# 00_Overview.net
KiCad netlist of a schematic drawn in Altium Designer
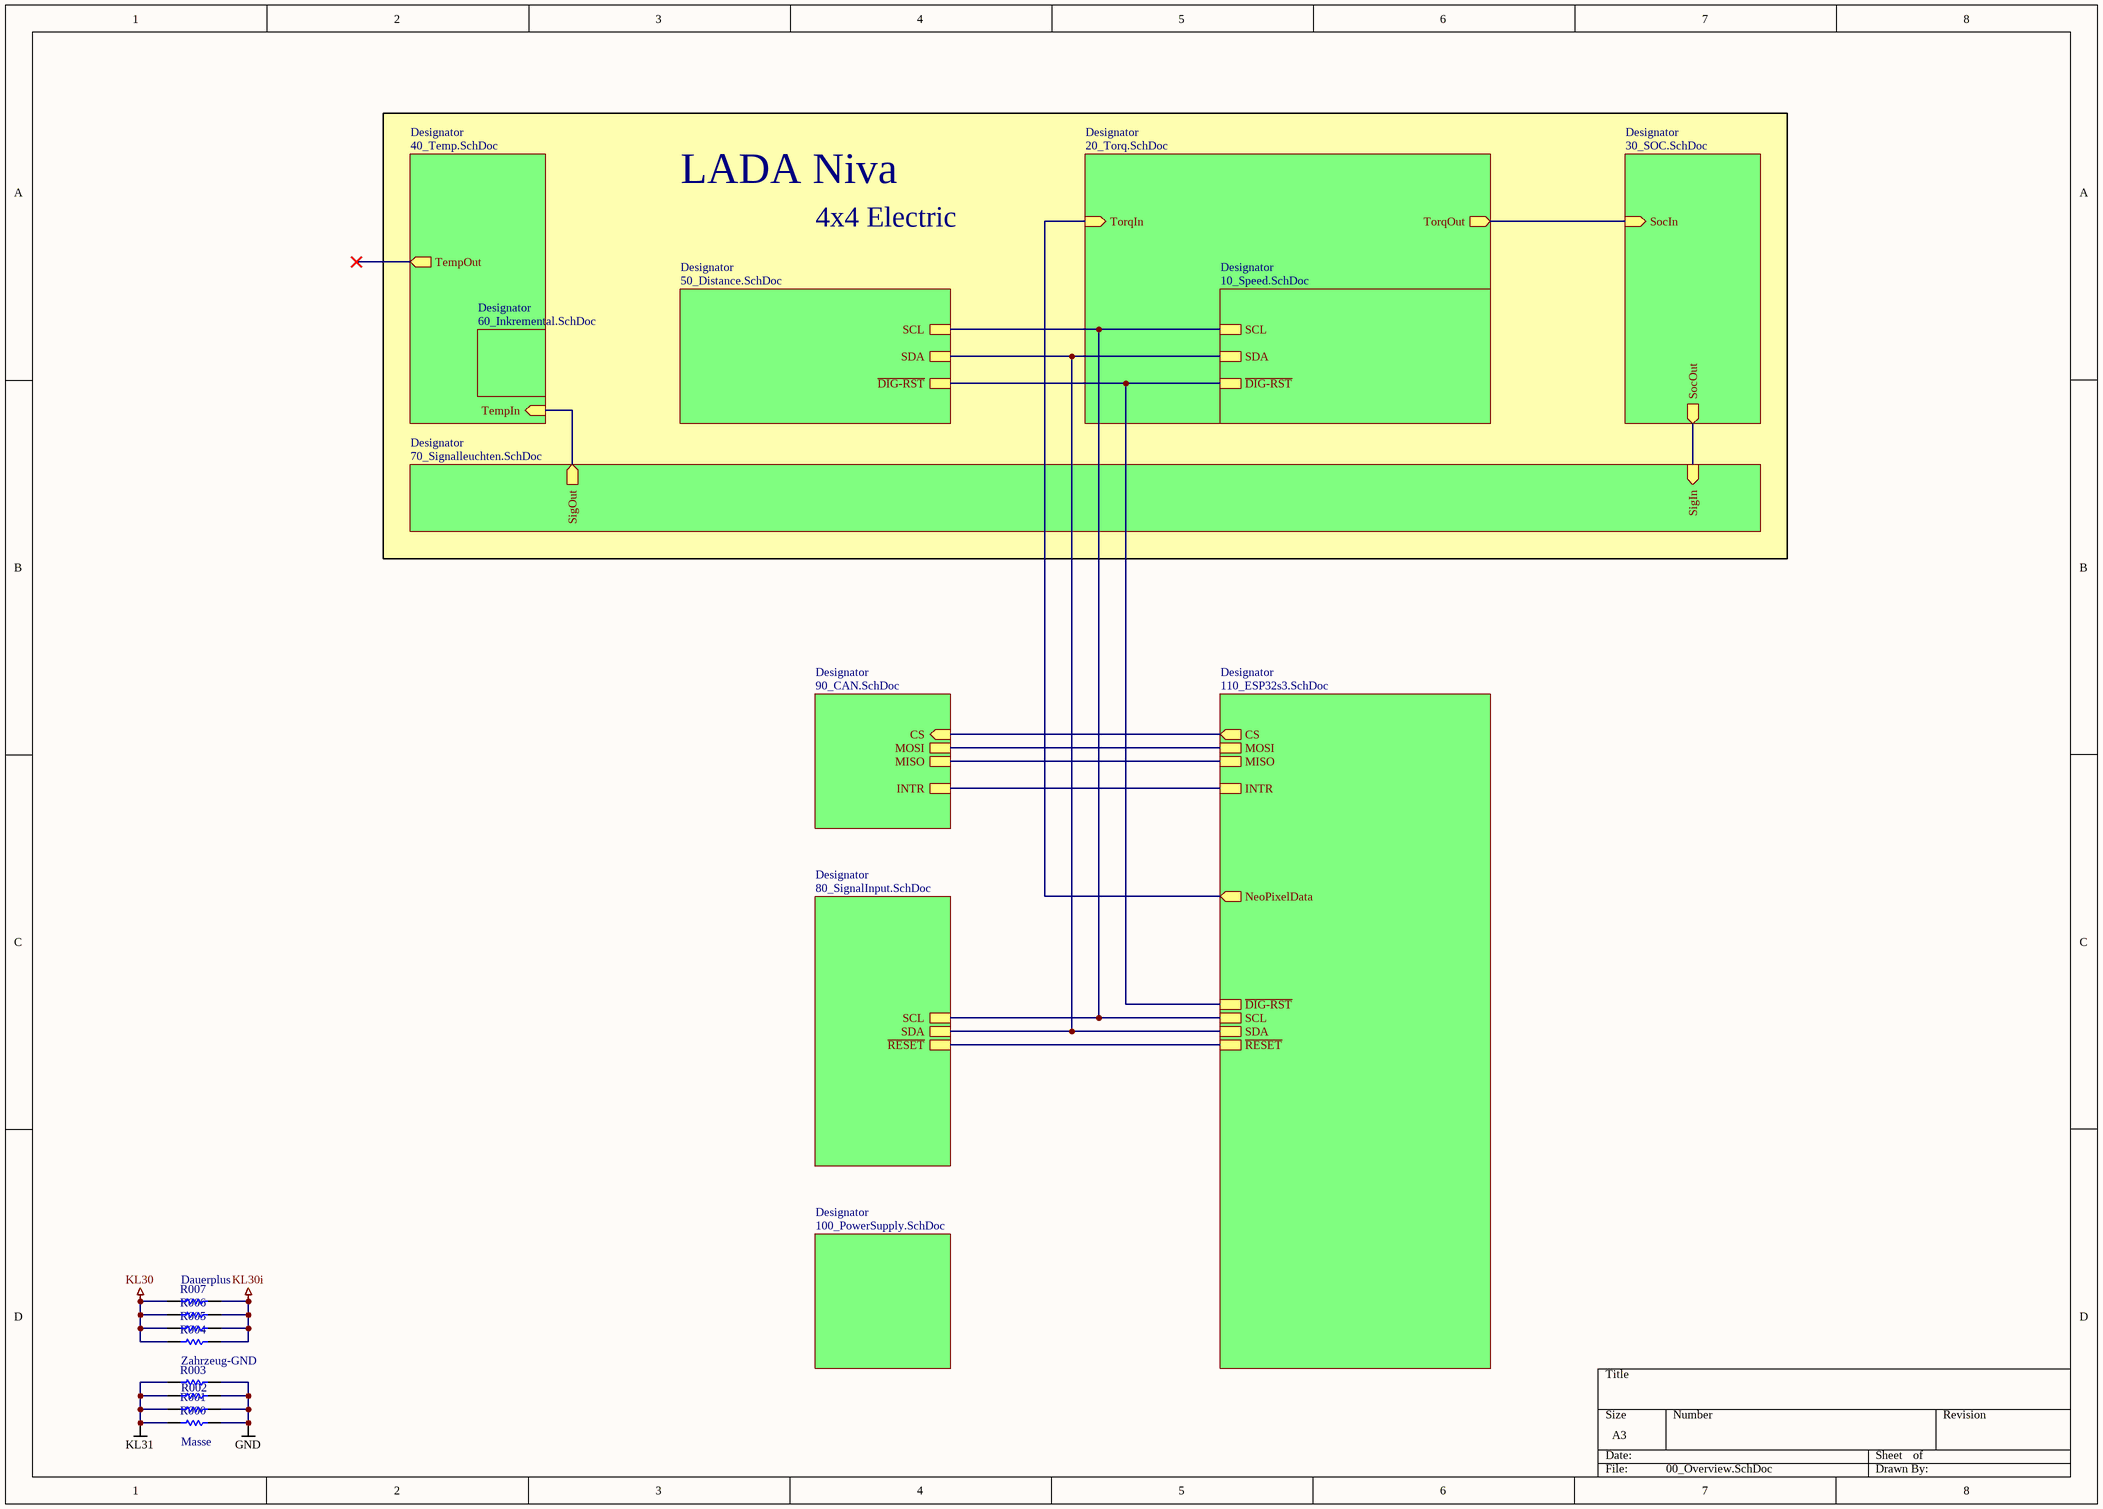
[diagram p0: 00_Overview.SchDoc]

(export (version "E")
  (design (tool "Eeschema 10.0.6"))
  (components
    (comp (ref "R000")
      (value "RC0603JR-070RL")
      (footprint "RESC1608X55X25ML10T15")
      (description "Chip Resistor, 0 Ohm, +/- 5%, 0.1 W, -55 to 155 degC, 0603 (1608 Metric), RoHS, Tape and Reel")
      (fields (field (name "TOLERANCE") "5%") (field (name "MANUFACTURER") "Yageo"))
      (libsource (lib "Altium Content Vault") (part "RES-2"))
    )
    (comp (ref "R001")
      (value "RC0603JR-070RL")
      (footprint "RESC1608X55X25ML10T15")
      (description "Chip Resistor, 0 Ohm, +/- 5%, 0.1 W, -55 to 155 degC, 0603 (1608 Metric), RoHS, Tape and Reel")
      (fields (field (name "TOLERANCE") "5%") (field (name "MANUFACTURER") "Yageo"))
      (libsource (lib "Altium Content Vault") (part "RES-2"))
    )
    (comp (ref "R002")
      (value "RC0603JR-070RL")
      (footprint "RESC1608X55X25ML10T15")
      (description "Chip Resistor, 0 Ohm, +/- 5%, 0.1 W, -55 to 155 degC, 0603 (1608 Metric), RoHS, Tape and Reel")
      (fields (field (name "TOLERANCE") "5%") (field (name "MANUFACTURER") "Yageo"))
      (libsource (lib "Altium Content Vault") (part "RES-2"))
    )
    (comp (ref "R003")
      (value "RC0603JR-070RL")
      (footprint "RESC1608X55X25ML10T15")
      (description "Chip Resistor, 0 Ohm, +/- 5%, 0.1 W, -55 to 155 degC, 0603 (1608 Metric), RoHS, Tape and Reel")
      (fields (field (name "TOLERANCE") "5%") (field (name "MANUFACTURER") "Yageo"))
      (libsource (lib "Altium Content Vault") (part "RES-2"))
    )
    (comp (ref "R004")
      (value "RC0603JR-070RL")
      (footprint "RESC1608X55X25ML10T15")
      (description "Chip Resistor, 0 Ohm, +/- 5%, 0.1 W, -55 to 155 degC, 0603 (1608 Metric), RoHS, Tape and Reel")
      (fields (field (name "TOLERANCE") "5%") (field (name "MANUFACTURER") "Yageo"))
      (libsource (lib "Altium Content Vault") (part "RES-2"))
    )
    (comp (ref "R005")
      (value "RC0603JR-070RL")
      (footprint "RESC1608X55X25ML10T15")
      (description "Chip Resistor, 0 Ohm, +/- 5%, 0.1 W, -55 to 155 degC, 0603 (1608 Metric), RoHS, Tape and Reel")
      (fields (field (name "TOLERANCE") "5%") (field (name "MANUFACTURER") "Yageo"))
      (libsource (lib "Altium Content Vault") (part "RES-2"))
    )
    (comp (ref "R006")
      (value "RC0603JR-070RL")
      (footprint "RESC1608X55X25ML10T15")
      (description "Chip Resistor, 0 Ohm, +/- 5%, 0.1 W, -55 to 155 degC, 0603 (1608 Metric), RoHS, Tape and Reel")
      (fields (field (name "TOLERANCE") "5%") (field (name "MANUFACTURER") "Yageo"))
      (libsource (lib "Altium Content Vault") (part "RES-2"))
    )
    (comp (ref "R007")
      (value "RC0603JR-070RL")
      (footprint "RESC1608X55X25ML10T15")
      (description "Chip Resistor, 0 Ohm, +/- 5%, 0.1 W, -55 to 155 degC, 0603 (1608 Metric), RoHS, Tape and Reel")
      (fields (field (name "TOLERANCE") "5%") (field (name "MANUFACTURER") "Yageo"))
      (libsource (lib "Altium Content Vault") (part "RES-2"))
    )
  )
  (nets
    (net (code "14") (name "GND") (class "Default")
      (node (ref "R000") (pin "2") (pinfunction "2_2") (pintype "passive"))
      (node (ref "R001") (pin "2") (pinfunction "2_2") (pintype "passive"))
      (node (ref "R002") (pin "2") (pinfunction "2_2") (pintype "passive"))
      (node (ref "R003") (pin "2") (pinfunction "2_2") (pintype "passive"))
    )
    (net (code "15") (name "KL30") (class "Default")
      (node (ref "R004") (pin "1") (pinfunction "1_1") (pintype "passive"))
      (node (ref "R005") (pin "1") (pinfunction "1_1") (pintype "passive"))
      (node (ref "R006") (pin "1") (pinfunction "1_1") (pintype "passive"))
      (node (ref "R007") (pin "1") (pinfunction "1_1") (pintype "passive"))
    )
    (net (code "16") (name "KL30i") (class "Default")
      (node (ref "R004") (pin "2") (pinfunction "2_2") (pintype "passive"))
      (node (ref "R005") (pin "2") (pinfunction "2_2") (pintype "passive"))
      (node (ref "R006") (pin "2") (pinfunction "2_2") (pintype "passive"))
      (node (ref "R007") (pin "2") (pinfunction "2_2") (pintype "passive"))
    )
    (net (code "17") (name "KL31") (class "Default")
      (node (ref "R000") (pin "1") (pinfunction "1_1") (pintype "passive"))
      (node (ref "R001") (pin "1") (pinfunction "1_1") (pintype "passive"))
      (node (ref "R002") (pin "1") (pinfunction "1_1") (pintype "passive"))
      (node (ref "R003") (pin "1") (pinfunction "1_1") (pintype "passive"))
    )
  )
)
